# buffered-mult-pcb-b.net
KiCad netlist of a schematic drawn in EAGLE
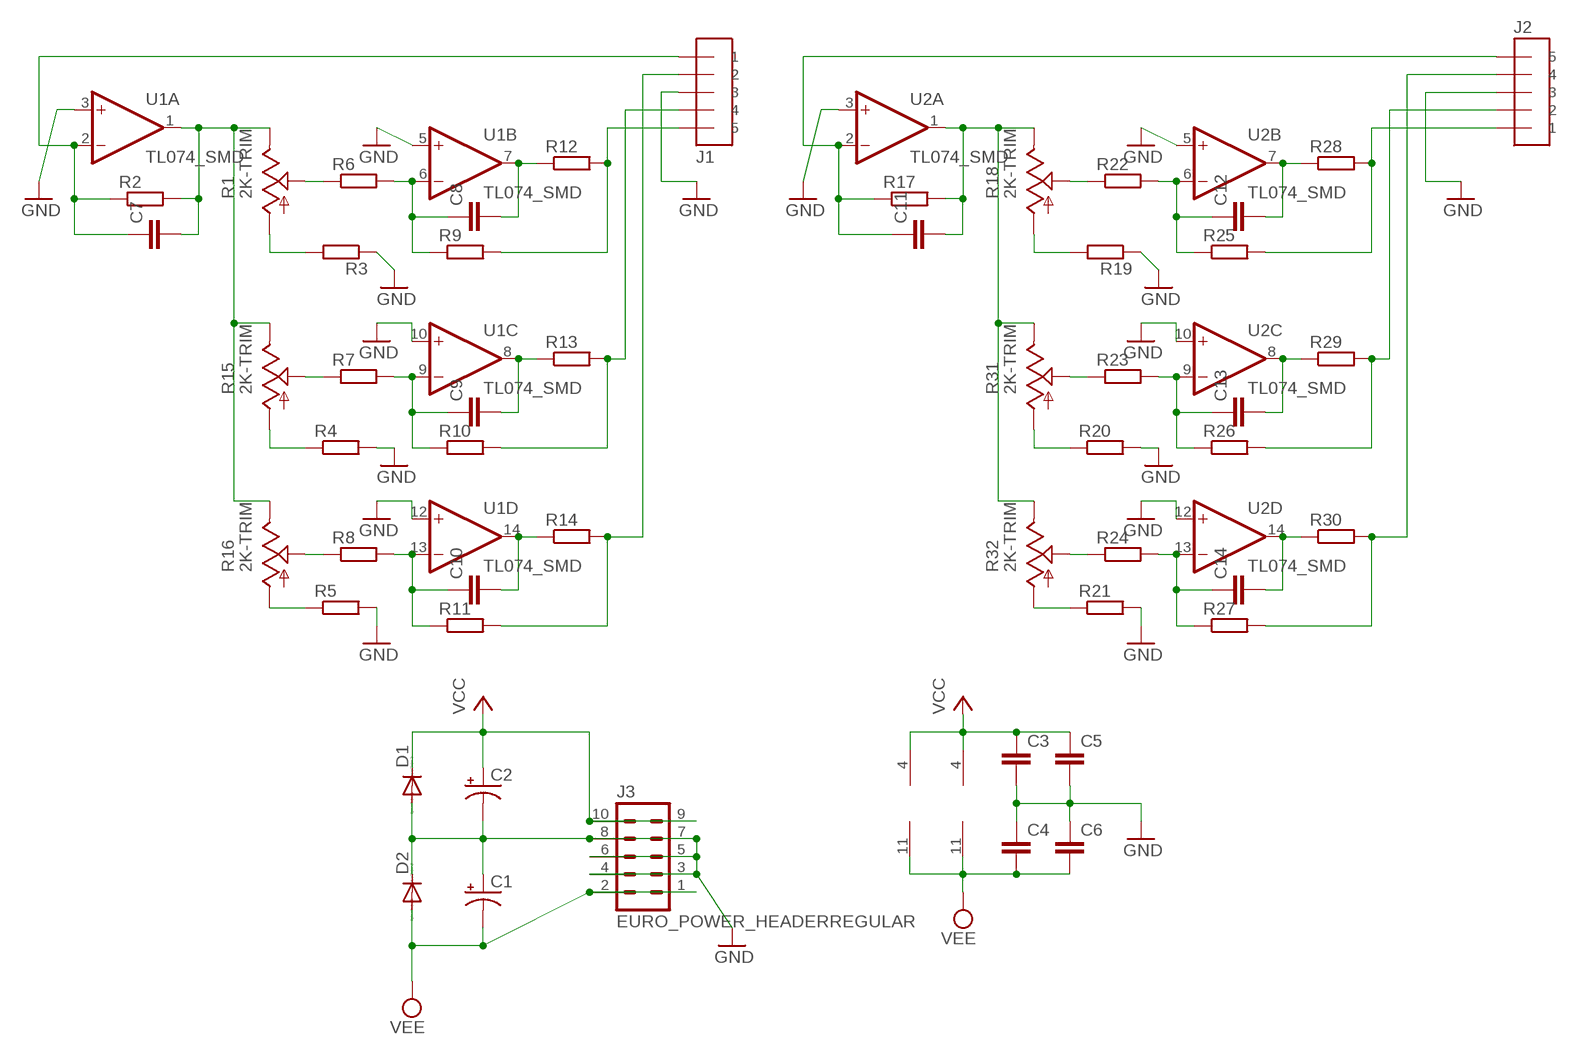
[diagram p0: schematic, sheet 1]

(export (version "E")
  (design (tool "Eeschema 10.0.6"))
  (components
    (comp (ref "C1")
      (value "CPOL-USD")
      (footprint "eagle-import:PANASONIC_D")
      (libsource (lib "eagle-import") (part "CPOL-USD"))
    )
    (comp (ref "C2")
      (value "CPOL-USD")
      (footprint "eagle-import:PANASONIC_D")
      (libsource (lib "eagle-import") (part "CPOL-USD"))
    )
    (comp (ref "C3")
      (value "C-EUC0603")
      (footprint "eagle-import:C0603")
      (libsource (lib "eagle-import") (part "C-EUC0603"))
    )
    (comp (ref "C4")
      (value "C-EUC0603")
      (footprint "eagle-import:C0603")
      (libsource (lib "eagle-import") (part "C-EUC0603"))
    )
    (comp (ref "C5")
      (value "C-EUC0603")
      (footprint "eagle-import:C0603")
      (libsource (lib "eagle-import") (part "C-EUC0603"))
    )
    (comp (ref "C6")
      (value "C-EUC0603")
      (footprint "eagle-import:C0603")
      (libsource (lib "eagle-import") (part "C-EUC0603"))
    )
    (comp (ref "C7")
      (value "C-EUC0603")
      (footprint "eagle-import:C0603")
      (libsource (lib "eagle-import") (part "C-EUC0603"))
    )
    (comp (ref "C8")
      (value "C-EUC0603")
      (footprint "eagle-import:C0603")
      (libsource (lib "eagle-import") (part "C-EUC0603"))
    )
    (comp (ref "C9")
      (value "C-EUC0603")
      (footprint "eagle-import:C0603")
      (libsource (lib "eagle-import") (part "C-EUC0603"))
    )
    (comp (ref "C10")
      (value "C-EUC0603")
      (footprint "eagle-import:C0603")
      (libsource (lib "eagle-import") (part "C-EUC0603"))
    )
    (comp (ref "C11")
      (value "C-EUC0603")
      (footprint "eagle-import:C0603")
      (libsource (lib "eagle-import") (part "C-EUC0603"))
    )
    (comp (ref "C12")
      (value "C-EUC0603")
      (footprint "eagle-import:C0603")
      (libsource (lib "eagle-import") (part "C-EUC0603"))
    )
    (comp (ref "C13")
      (value "C-EUC0603")
      (footprint "eagle-import:C0603")
      (libsource (lib "eagle-import") (part "C-EUC0603"))
    )
    (comp (ref "C14")
      (value "C-EUC0603")
      (footprint "eagle-import:C0603")
      (libsource (lib "eagle-import") (part "C-EUC0603"))
    )
    (comp (ref "D1")
      (value "DIODE-SOD123")
      (footprint "eagle-import:SOD123")
      (libsource (lib "eagle-import") (part "DIODE-SOD123"))
    )
    (comp (ref "D2")
      (value "DIODE-SOD123")
      (footprint "eagle-import:SOD123")
      (libsource (lib "eagle-import") (part "DIODE-SOD123"))
    )
    (comp (ref "J1")
      (value "5X1_2_54_HEADER")
      (footprint "eagle-import:5X1_2_54_HEADER")
      (libsource (lib "eagle-import") (part "5X1_2_54_HEADER"))
    )
    (comp (ref "J2")
      (value "5X1_2_54_HEADER")
      (footprint "eagle-import:5X1_2_54_HEADER")
      (libsource (lib "eagle-import") (part "5X1_2_54_HEADER"))
    )
    (comp (ref "J3")
      (value "EURO_POWER_HEADERREGULAR")
      (footprint "eagle-import:EURO_POWER_HEADER")
      (libsource (lib "eagle-import") (part "EURO_POWER_HEADERREGULAR"))
    )
    (comp (ref "R1")
      (value "2K-TRIM")
      (footprint "eagle-import:BOURNS_TRIM_3303X3_SMD")
      (libsource (lib "eagle-import") (part "BOURNS_TRIM_3303X3_SMD"))
    )
    (comp (ref "R2")
      (value "R-EU_R0603")
      (footprint "eagle-import:R0603")
      (libsource (lib "eagle-import") (part "R-EU_R0603"))
    )
    (comp (ref "R3")
      (value "R-EU_R0603")
      (footprint "eagle-import:R0603")
      (libsource (lib "eagle-import") (part "R-EU_R0603"))
    )
    (comp (ref "R4")
      (value "R-EU_R0603")
      (footprint "eagle-import:R0603")
      (libsource (lib "eagle-import") (part "R-EU_R0603"))
    )
    (comp (ref "R5")
      (value "R-EU_R0603")
      (footprint "eagle-import:R0603")
      (libsource (lib "eagle-import") (part "R-EU_R0603"))
    )
    (comp (ref "R6")
      (value "R-EU_R0603")
      (footprint "eagle-import:R0603")
      (libsource (lib "eagle-import") (part "R-EU_R0603"))
    )
    (comp (ref "R7")
      (value "R-EU_R0603")
      (footprint "eagle-import:R0603")
      (libsource (lib "eagle-import") (part "R-EU_R0603"))
    )
    (comp (ref "R8")
      (value "R-EU_R0603")
      (footprint "eagle-import:R0603")
      (libsource (lib "eagle-import") (part "R-EU_R0603"))
    )
    (comp (ref "R9")
      (value "R-EU_R0603")
      (footprint "eagle-import:R0603")
      (libsource (lib "eagle-import") (part "R-EU_R0603"))
    )
    (comp (ref "R10")
      (value "R-EU_R0603")
      (footprint "eagle-import:R0603")
      (libsource (lib "eagle-import") (part "R-EU_R0603"))
    )
    (comp (ref "R11")
      (value "R-EU_R0603")
      (footprint "eagle-import:R0603")
      (libsource (lib "eagle-import") (part "R-EU_R0603"))
    )
    (comp (ref "R12")
      (value "R-EU_R0603")
      (footprint "eagle-import:R0603")
      (libsource (lib "eagle-import") (part "R-EU_R0603"))
    )
    (comp (ref "R13")
      (value "R-EU_R0603")
      (footprint "eagle-import:R0603")
      (libsource (lib "eagle-import") (part "R-EU_R0603"))
    )
    (comp (ref "R14")
      (value "R-EU_R0603")
      (footprint "eagle-import:R0603")
      (libsource (lib "eagle-import") (part "R-EU_R0603"))
    )
    (comp (ref "R15")
      (value "2K-TRIM")
      (footprint "eagle-import:BOURNS_TRIM_3303X3_SMD")
      (libsource (lib "eagle-import") (part "BOURNS_TRIM_3303X3_SMD"))
    )
    (comp (ref "R16")
      (value "2K-TRIM")
      (footprint "eagle-import:BOURNS_TRIM_3303X3_SMD")
      (libsource (lib "eagle-import") (part "BOURNS_TRIM_3303X3_SMD"))
    )
    (comp (ref "R17")
      (value "R-EU_R0603")
      (footprint "eagle-import:R0603")
      (libsource (lib "eagle-import") (part "R-EU_R0603"))
    )
    (comp (ref "R18")
      (value "2K-TRIM")
      (footprint "eagle-import:BOURNS_TRIM_3303X3_SMD")
      (libsource (lib "eagle-import") (part "BOURNS_TRIM_3303X3_SMD"))
    )
    (comp (ref "R19")
      (value "R-EU_R0603")
      (footprint "eagle-import:R0603")
      (libsource (lib "eagle-import") (part "R-EU_R0603"))
    )
    (comp (ref "R20")
      (value "R-EU_R0603")
      (footprint "eagle-import:R0603")
      (libsource (lib "eagle-import") (part "R-EU_R0603"))
    )
    (comp (ref "R21")
      (value "R-EU_R0603")
      (footprint "eagle-import:R0603")
      (libsource (lib "eagle-import") (part "R-EU_R0603"))
    )
    (comp (ref "R22")
      (value "R-EU_R0603")
      (footprint "eagle-import:R0603")
      (libsource (lib "eagle-import") (part "R-EU_R0603"))
    )
    (comp (ref "R23")
      (value "R-EU_R0603")
      (footprint "eagle-import:R0603")
      (libsource (lib "eagle-import") (part "R-EU_R0603"))
    )
    (comp (ref "R24")
      (value "R-EU_R0603")
      (footprint "eagle-import:R0603")
      (libsource (lib "eagle-import") (part "R-EU_R0603"))
    )
    (comp (ref "R25")
      (value "R-EU_R0603")
      (footprint "eagle-import:R0603")
      (libsource (lib "eagle-import") (part "R-EU_R0603"))
    )
    (comp (ref "R26")
      (value "R-EU_R0603")
      (footprint "eagle-import:R0603")
      (libsource (lib "eagle-import") (part "R-EU_R0603"))
    )
    (comp (ref "R27")
      (value "R-EU_R0603")
      (footprint "eagle-import:R0603")
      (libsource (lib "eagle-import") (part "R-EU_R0603"))
    )
    (comp (ref "R28")
      (value "R-EU_R0603")
      (footprint "eagle-import:R0603")
      (libsource (lib "eagle-import") (part "R-EU_R0603"))
    )
    (comp (ref "R29")
      (value "R-EU_R0603")
      (footprint "eagle-import:R0603")
      (libsource (lib "eagle-import") (part "R-EU_R0603"))
    )
    (comp (ref "R30")
      (value "R-EU_R0603")
      (footprint "eagle-import:R0603")
      (libsource (lib "eagle-import") (part "R-EU_R0603"))
    )
    (comp (ref "R31")
      (value "2K-TRIM")
      (footprint "eagle-import:BOURNS_TRIM_3303X3_SMD")
      (libsource (lib "eagle-import") (part "BOURNS_TRIM_3303X3_SMD"))
    )
    (comp (ref "R32")
      (value "2K-TRIM")
      (footprint "eagle-import:BOURNS_TRIM_3303X3_SMD")
      (libsource (lib "eagle-import") (part "BOURNS_TRIM_3303X3_SMD"))
    )
    (comp (ref "U1")
      (value "TL074_SMD")
      (footprint "eagle-import:SO14")
      (libsource (lib "eagle-import") (part "TL074_SMD"))
    )
    (comp (ref "U2")
      (value "TL074_SMD")
      (footprint "eagle-import:SO14")
      (libsource (lib "eagle-import") (part "TL074_SMD"))
    )
  )
  (nets
    (net (code "1") (name "GND") (class "Default")
      (node (ref "C1") (pin "+") (pinfunction "+_+") (pintype "passive"))
      (node (ref "C2") (pin "-") (pinfunction "-_-") (pintype "passive"))
      (node (ref "C3") (pin "2") (pinfunction "2_2") (pintype "passive"))
      (node (ref "C4") (pin "1") (pinfunction "1_1") (pintype "passive"))
      (node (ref "C5") (pin "2") (pinfunction "2_2") (pintype "passive"))
      (node (ref "C6") (pin "1") (pinfunction "1_1") (pintype "passive"))
      (node (ref "D1") (pin "A") (pinfunction "A_A") (pintype "passive"))
      (node (ref "D2") (pin "C") (pinfunction "C_C") (pintype "passive"))
      (node (ref "J1") (pin "3") (pinfunction "3_3") (pintype "bidirectional"))
      (node (ref "J2") (pin "3") (pinfunction "3_3") (pintype "bidirectional"))
      (node (ref "J3") (pin "3") (pinfunction "3_3") (pintype "passive"))
      (node (ref "J3") (pin "4") (pinfunction "4_4") (pintype "passive"))
      (node (ref "J3") (pin "5") (pinfunction "5_5") (pintype "passive"))
      (node (ref "J3") (pin "6") (pinfunction "6_6") (pintype "passive"))
      (node (ref "J3") (pin "7") (pinfunction "7_7") (pintype "passive"))
      (node (ref "J3") (pin "8") (pinfunction "8_8") (pintype "passive"))
      (node (ref "R19") (pin "1") (pinfunction "1_1") (pintype "passive"))
      (node (ref "R20") (pin "2") (pinfunction "2_2") (pintype "passive"))
      (node (ref "R21") (pin "2") (pinfunction "2_2") (pintype "passive"))
      (node (ref "R3") (pin "1") (pinfunction "1_1") (pintype "passive"))
      (node (ref "R4") (pin "2") (pinfunction "2_2") (pintype "passive"))
      (node (ref "R5") (pin "2") (pinfunction "2_2") (pintype "passive"))
      (node (ref "U1") (pin "10") (pinfunction "+IN_10") (pintype "input"))
      (node (ref "U1") (pin "12") (pinfunction "+IN_12") (pintype "input"))
      (node (ref "U1") (pin "3") (pinfunction "+IN_3") (pintype "input"))
      (node (ref "U1") (pin "5") (pinfunction "+IN_5") (pintype "input"))
      (node (ref "U2") (pin "10") (pinfunction "+IN_10") (pintype "input"))
      (node (ref "U2") (pin "12") (pinfunction "+IN_12") (pintype "input"))
      (node (ref "U2") (pin "3") (pinfunction "+IN_3") (pintype "input"))
      (node (ref "U2") (pin "5") (pinfunction "+IN_5") (pintype "input"))
    )
    (net (code "2") (name "Net-(J1-Pad2)") (class "Default")
      (node (ref "J1") (pin "2") (pinfunction "2_2") (pintype "bidirectional"))
      (node (ref "R11") (pin "2") (pinfunction "2_2") (pintype "passive"))
      (node (ref "R14") (pin "2") (pinfunction "2_2") (pintype "passive"))
    )
    (net (code "3") (name "Net-(J1-Pad4)") (class "Default")
      (node (ref "J1") (pin "4") (pinfunction "4_4") (pintype "bidirectional"))
      (node (ref "R10") (pin "2") (pinfunction "2_2") (pintype "passive"))
      (node (ref "R13") (pin "2") (pinfunction "2_2") (pintype "passive"))
    )
    (net (code "4") (name "Net-(J1-Pad5)") (class "Default")
      (node (ref "J1") (pin "5") (pinfunction "5_5") (pintype "bidirectional"))
      (node (ref "R12") (pin "2") (pinfunction "2_2") (pintype "passive"))
      (node (ref "R9") (pin "2") (pinfunction "2_2") (pintype "passive"))
    )
    (net (code "5") (name "Net-(J2-Pad1)") (class "Default")
      (node (ref "J2") (pin "1") (pinfunction "1_1") (pintype "bidirectional"))
      (node (ref "R25") (pin "2") (pinfunction "2_2") (pintype "passive"))
      (node (ref "R28") (pin "2") (pinfunction "2_2") (pintype "passive"))
    )
    (net (code "6") (name "Net-(J2-Pad2)") (class "Default")
      (node (ref "J2") (pin "2") (pinfunction "2_2") (pintype "bidirectional"))
      (node (ref "R26") (pin "2") (pinfunction "2_2") (pintype "passive"))
      (node (ref "R29") (pin "2") (pinfunction "2_2") (pintype "passive"))
    )
    (net (code "7") (name "Net-(J2-Pad4)") (class "Default")
      (node (ref "J2") (pin "4") (pinfunction "4_4") (pintype "bidirectional"))
      (node (ref "R27") (pin "2") (pinfunction "2_2") (pintype "passive"))
      (node (ref "R30") (pin "2") (pinfunction "2_2") (pintype "passive"))
    )
    (net (code "8") (name "Net-(R1-A)") (class "Default")
      (node (ref "R1") (pin "3") (pinfunction "A_3") (pintype "passive"))
      (node (ref "R3") (pin "2") (pinfunction "2_2") (pintype "passive"))
    )
    (net (code "9") (name "Net-(R1-E)") (class "Default")
      (node (ref "C7") (pin "2") (pinfunction "2_2") (pintype "passive"))
      (node (ref "R1") (pin "1") (pinfunction "E_1") (pintype "passive"))
      (node (ref "R15") (pin "1") (pinfunction "E_1") (pintype "passive"))
      (node (ref "R16") (pin "1") (pinfunction "E_1") (pintype "passive"))
      (node (ref "R2") (pin "2") (pinfunction "2_2") (pintype "passive"))
      (node (ref "U1") (pin "1") (pinfunction "OUT_1") (pintype "output"))
    )
    (net (code "10") (name "Net-(R1-S)") (class "Default")
      (node (ref "R1") (pin "2") (pinfunction "S_2") (pintype "passive"))
      (node (ref "R6") (pin "1") (pinfunction "1_1") (pintype "passive"))
    )
    (net (code "11") (name "Net-(R15-A)") (class "Default")
      (node (ref "R15") (pin "3") (pinfunction "A_3") (pintype "passive"))
      (node (ref "R4") (pin "1") (pinfunction "1_1") (pintype "passive"))
    )
    (net (code "12") (name "Net-(R15-S)") (class "Default")
      (node (ref "R15") (pin "2") (pinfunction "S_2") (pintype "passive"))
      (node (ref "R7") (pin "1") (pinfunction "1_1") (pintype "passive"))
    )
    (net (code "13") (name "Net-(R16-A)") (class "Default")
      (node (ref "R16") (pin "3") (pinfunction "A_3") (pintype "passive"))
      (node (ref "R5") (pin "1") (pinfunction "1_1") (pintype "passive"))
    )
    (net (code "14") (name "Net-(R16-S)") (class "Default")
      (node (ref "R16") (pin "2") (pinfunction "S_2") (pintype "passive"))
      (node (ref "R8") (pin "1") (pinfunction "1_1") (pintype "passive"))
    )
    (net (code "15") (name "Net-(R18-A)") (class "Default")
      (node (ref "R18") (pin "3") (pinfunction "A_3") (pintype "passive"))
      (node (ref "R19") (pin "2") (pinfunction "2_2") (pintype "passive"))
    )
    (net (code "16") (name "Net-(R18-E)") (class "Default")
      (node (ref "C11") (pin "2") (pinfunction "2_2") (pintype "passive"))
      (node (ref "R17") (pin "2") (pinfunction "2_2") (pintype "passive"))
      (node (ref "R18") (pin "1") (pinfunction "E_1") (pintype "passive"))
      (node (ref "R31") (pin "1") (pinfunction "E_1") (pintype "passive"))
      (node (ref "R32") (pin "1") (pinfunction "E_1") (pintype "passive"))
      (node (ref "U2") (pin "1") (pinfunction "OUT_1") (pintype "output"))
    )
    (net (code "17") (name "Net-(R18-S)") (class "Default")
      (node (ref "R18") (pin "2") (pinfunction "S_2") (pintype "passive"))
      (node (ref "R22") (pin "1") (pinfunction "1_1") (pintype "passive"))
    )
    (net (code "18") (name "Net-(R31-A)") (class "Default")
      (node (ref "R20") (pin "1") (pinfunction "1_1") (pintype "passive"))
      (node (ref "R31") (pin "3") (pinfunction "A_3") (pintype "passive"))
    )
    (net (code "19") (name "Net-(R31-S)") (class "Default")
      (node (ref "R23") (pin "1") (pinfunction "1_1") (pintype "passive"))
      (node (ref "R31") (pin "2") (pinfunction "S_2") (pintype "passive"))
    )
    (net (code "20") (name "Net-(R32-A)") (class "Default")
      (node (ref "R21") (pin "1") (pinfunction "1_1") (pintype "passive"))
      (node (ref "R32") (pin "3") (pinfunction "A_3") (pintype "passive"))
    )
    (net (code "21") (name "Net-(R32-S)") (class "Default")
      (node (ref "R24") (pin "1") (pinfunction "1_1") (pintype "passive"))
      (node (ref "R32") (pin "2") (pinfunction "S_2") (pintype "passive"))
    )
    (net (code "22") (name "Net-(U1A--IN)") (class "Default")
      (node (ref "C7") (pin "1") (pinfunction "1_1") (pintype "passive"))
      (node (ref "J1") (pin "1") (pinfunction "1_1") (pintype "bidirectional"))
      (node (ref "R2") (pin "1") (pinfunction "1_1") (pintype "passive"))
      (node (ref "U1") (pin "2") (pinfunction "-IN_2") (pintype "input"))
    )
    (net (code "23") (name "Net-(U1B--IN)") (class "Default")
      (node (ref "C8") (pin "1") (pinfunction "1_1") (pintype "passive"))
      (node (ref "R6") (pin "2") (pinfunction "2_2") (pintype "passive"))
      (node (ref "R9") (pin "1") (pinfunction "1_1") (pintype "passive"))
      (node (ref "U1") (pin "6") (pinfunction "-IN_6") (pintype "input"))
    )
    (net (code "24") (name "Net-(U1B-OUT)") (class "Default")
      (node (ref "C8") (pin "2") (pinfunction "2_2") (pintype "passive"))
      (node (ref "R12") (pin "1") (pinfunction "1_1") (pintype "passive"))
      (node (ref "U1") (pin "7") (pinfunction "OUT_7") (pintype "output"))
    )
    (net (code "25") (name "Net-(U1C--IN)") (class "Default")
      (node (ref "C9") (pin "1") (pinfunction "1_1") (pintype "passive"))
      (node (ref "R10") (pin "1") (pinfunction "1_1") (pintype "passive"))
      (node (ref "R7") (pin "2") (pinfunction "2_2") (pintype "passive"))
      (node (ref "U1") (pin "9") (pinfunction "-IN_9") (pintype "input"))
    )
    (net (code "26") (name "Net-(U1C-OUT)") (class "Default")
      (node (ref "C9") (pin "2") (pinfunction "2_2") (pintype "passive"))
      (node (ref "R13") (pin "1") (pinfunction "1_1") (pintype "passive"))
      (node (ref "U1") (pin "8") (pinfunction "OUT_8") (pintype "output"))
    )
    (net (code "27") (name "Net-(U1D--IN)") (class "Default")
      (node (ref "C10") (pin "1") (pinfunction "1_1") (pintype "passive"))
      (node (ref "R11") (pin "1") (pinfunction "1_1") (pintype "passive"))
      (node (ref "R8") (pin "2") (pinfunction "2_2") (pintype "passive"))
      (node (ref "U1") (pin "13") (pinfunction "-IN_13") (pintype "input"))
    )
    (net (code "28") (name "Net-(U1D-OUT)") (class "Default")
      (node (ref "C10") (pin "2") (pinfunction "2_2") (pintype "passive"))
      (node (ref "R14") (pin "1") (pinfunction "1_1") (pintype "passive"))
      (node (ref "U1") (pin "14") (pinfunction "OUT_14") (pintype "output"))
    )
    (net (code "29") (name "Net-(U2A--IN)") (class "Default")
      (node (ref "C11") (pin "1") (pinfunction "1_1") (pintype "passive"))
      (node (ref "J2") (pin "5") (pinfunction "5_5") (pintype "bidirectional"))
      (node (ref "R17") (pin "1") (pinfunction "1_1") (pintype "passive"))
      (node (ref "U2") (pin "2") (pinfunction "-IN_2") (pintype "input"))
    )
    (net (code "30") (name "Net-(U2B--IN)") (class "Default")
      (node (ref "C12") (pin "1") (pinfunction "1_1") (pintype "passive"))
      (node (ref "R22") (pin "2") (pinfunction "2_2") (pintype "passive"))
      (node (ref "R25") (pin "1") (pinfunction "1_1") (pintype "passive"))
      (node (ref "U2") (pin "6") (pinfunction "-IN_6") (pintype "input"))
    )
    (net (code "31") (name "Net-(U2B-OUT)") (class "Default")
      (node (ref "C12") (pin "2") (pinfunction "2_2") (pintype "passive"))
      (node (ref "R28") (pin "1") (pinfunction "1_1") (pintype "passive"))
      (node (ref "U2") (pin "7") (pinfunction "OUT_7") (pintype "output"))
    )
    (net (code "32") (name "Net-(U2C--IN)") (class "Default")
      (node (ref "C13") (pin "1") (pinfunction "1_1") (pintype "passive"))
      (node (ref "R23") (pin "2") (pinfunction "2_2") (pintype "passive"))
      (node (ref "R26") (pin "1") (pinfunction "1_1") (pintype "passive"))
      (node (ref "U2") (pin "9") (pinfunction "-IN_9") (pintype "input"))
    )
    (net (code "33") (name "Net-(U2C-OUT)") (class "Default")
      (node (ref "C13") (pin "2") (pinfunction "2_2") (pintype "passive"))
      (node (ref "R29") (pin "1") (pinfunction "1_1") (pintype "passive"))
      (node (ref "U2") (pin "8") (pinfunction "OUT_8") (pintype "output"))
    )
    (net (code "34") (name "Net-(U2D--IN)") (class "Default")
      (node (ref "C14") (pin "1") (pinfunction "1_1") (pintype "passive"))
      (node (ref "R24") (pin "2") (pinfunction "2_2") (pintype "passive"))
      (node (ref "R27") (pin "1") (pinfunction "1_1") (pintype "passive"))
      (node (ref "U2") (pin "13") (pinfunction "-IN_13") (pintype "input"))
    )
    (net (code "35") (name "Net-(U2D-OUT)") (class "Default")
      (node (ref "C14") (pin "2") (pinfunction "2_2") (pintype "passive"))
      (node (ref "R30") (pin "1") (pinfunction "1_1") (pintype "passive"))
      (node (ref "U2") (pin "14") (pinfunction "OUT_14") (pintype "output"))
    )
    (net (code "36") (name "VCC") (class "Default")
      (node (ref "C2") (pin "+") (pinfunction "+_+") (pintype "passive"))
      (node (ref "C3") (pin "1") (pinfunction "1_1") (pintype "passive"))
      (node (ref "C5") (pin "1") (pinfunction "1_1") (pintype "passive"))
      (node (ref "D1") (pin "C") (pinfunction "C_C") (pintype "passive"))
      (node (ref "J3") (pin "10") (pinfunction "10_10") (pintype "passive"))
      (node (ref "J3") (pin "9") (pinfunction "9_9") (pintype "passive"))
      (node (ref "U1") (pin "4") (pinfunction "V+_4") (pintype "power_in"))
      (node (ref "U2") (pin "4") (pinfunction "V+_4") (pintype "power_in"))
    )
    (net (code "37") (name "VEE") (class "Default")
      (node (ref "C1") (pin "-") (pinfunction "-_-") (pintype "passive"))
      (node (ref "C4") (pin "2") (pinfunction "2_2") (pintype "passive"))
      (node (ref "C6") (pin "2") (pinfunction "2_2") (pintype "passive"))
      (node (ref "D2") (pin "A") (pinfunction "A_A") (pintype "passive"))
      (node (ref "J3") (pin "1") (pinfunction "1_1") (pintype "passive"))
      (node (ref "J3") (pin "2") (pinfunction "2_2") (pintype "passive"))
      (node (ref "U1") (pin "11") (pinfunction "V-_11") (pintype "power_in"))
      (node (ref "U2") (pin "11") (pinfunction "V-_11") (pintype "power_in"))
    )
  )
)
